# Buttons.net
KiCad netlist of a schematic drawn in EAGLE
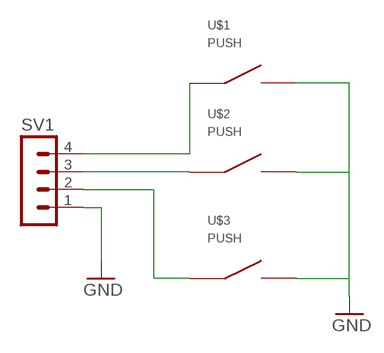
[diagram p0: schematic, sheet 1]

(export (version "E")
  (design (tool "Eeschema 10.0.6"))
  (components
    (comp (ref "SV1")
      (value "MA04-1W")
      (footprint "eagle-import:MA04-1W")
      (libsource (lib "eagle-import") (part "MA04-1W"))
    )
    (comp (ref "U$1")
      (value "PUSH")
      (footprint "eagle-import:PUSH")
      (libsource (lib "eagle-import") (part "PUSH"))
    )
    (comp (ref "U$2")
      (value "PUSH")
      (footprint "eagle-import:PUSH")
      (libsource (lib "eagle-import") (part "PUSH"))
    )
    (comp (ref "U$3")
      (value "PUSH")
      (footprint "eagle-import:PUSH")
      (libsource (lib "eagle-import") (part "PUSH"))
    )
  )
  (nets
    (net (code "1") (name "GND") (class "Default")
      (node (ref "SV1") (pin "1") (pinfunction "1_1") (pintype "passive"))
      (node (ref "U$1") (pin "3") (pinfunction "2_3") (pintype "bidirectional"))
      (node (ref "U$1") (pin "4") (pinfunction "2_4") (pintype "bidirectional"))
      (node (ref "U$2") (pin "3") (pinfunction "2_3") (pintype "bidirectional"))
      (node (ref "U$2") (pin "4") (pinfunction "2_4") (pintype "bidirectional"))
      (node (ref "U$3") (pin "3") (pinfunction "2_3") (pintype "bidirectional"))
      (node (ref "U$3") (pin "4") (pinfunction "2_4") (pintype "bidirectional"))
    )
    (net (code "2") (name "Net-(SV1-Pad2)") (class "Default")
      (node (ref "SV1") (pin "2") (pinfunction "2_2") (pintype "passive"))
      (node (ref "U$3") (pin "1") (pinfunction "1_1") (pintype "bidirectional"))
      (node (ref "U$3") (pin "2") (pinfunction "1_2") (pintype "bidirectional"))
    )
    (net (code "3") (name "Net-(SV1-Pad3)") (class "Default")
      (node (ref "SV1") (pin "3") (pinfunction "3_3") (pintype "passive"))
      (node (ref "U$2") (pin "1") (pinfunction "1_1") (pintype "bidirectional"))
      (node (ref "U$2") (pin "2") (pinfunction "1_2") (pintype "bidirectional"))
    )
    (net (code "4") (name "Net-(SV1-Pad4)") (class "Default")
      (node (ref "SV1") (pin "4") (pinfunction "4_4") (pintype "passive"))
      (node (ref "U$1") (pin "1") (pinfunction "1_1") (pintype "bidirectional"))
      (node (ref "U$1") (pin "2") (pinfunction "1_2") (pintype "bidirectional"))
    )
  )
)
